# CONTROL.net
KiCad netlist of a schematic drawn in EAGLE
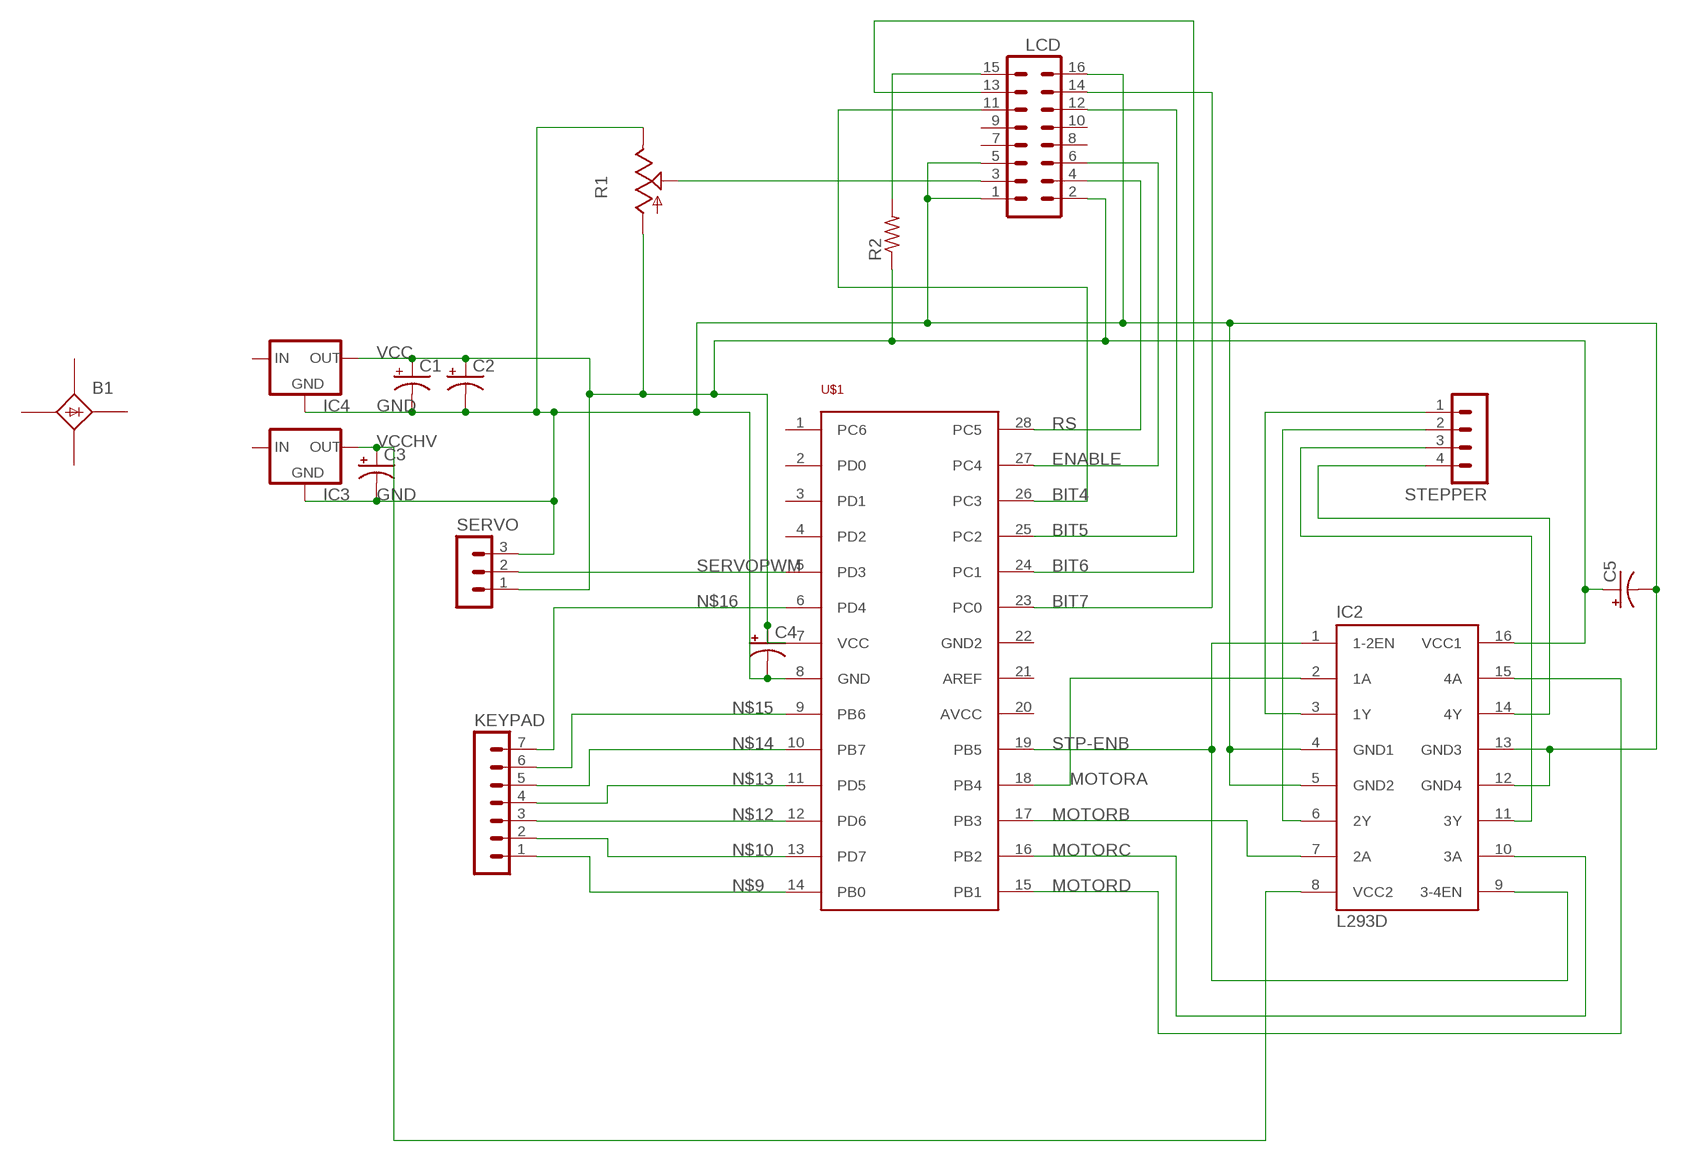
[diagram p0: schematic, sheet 1]

(export (version "E")
  (design (tool "Eeschema 10.0.6"))
  (components
    (comp (ref "B1")
      (value "B25A-")
      (footprint "eagle-import:B25A-")
      (libsource (lib "eagle-import") (part "B25A-"))
    )
    (comp (ref "C1")
      (value "CPOL-USE5-8.5")
      (footprint "eagle-import:E5-8,5")
      (libsource (lib "eagle-import") (part "CPOL-USE5-8.5"))
    )
    (comp (ref "C2")
      (value "CPOL-USE5-8.5")
      (footprint "eagle-import:E5-8,5")
      (libsource (lib "eagle-import") (part "CPOL-USE5-8.5"))
    )
    (comp (ref "C3")
      (value "CPOL-USE5-8.5")
      (footprint "eagle-import:E5-8,5")
      (libsource (lib "eagle-import") (part "CPOL-USE5-8.5"))
    )
    (comp (ref "C4")
      (value "CPOL-USE5-8.5")
      (footprint "eagle-import:E5-8,5")
      (libsource (lib "eagle-import") (part "CPOL-USE5-8.5"))
    )
    (comp (ref "C5")
      (value "CPOL-USE5-8.5")
      (footprint "eagle-import:E5-8,5")
      (libsource (lib "eagle-import") (part "CPOL-USE5-8.5"))
    )
    (comp (ref "IC2")
      (value "L293D")
      (footprint "eagle-import:DIL16")
      (libsource (lib "eagle-import") (part "L293D"))
    )
    (comp (ref "IC3")
      (value "78XXS")
      (footprint "eagle-import:78XXS")
      (libsource (lib "eagle-import") (part "78XXS"))
    )
    (comp (ref "IC4")
      (value "78XXS")
      (footprint "eagle-import:78XXS")
      (libsource (lib "eagle-import") (part "78XXS"))
    )
    (comp (ref "KEYPAD")
      (value "MA07-1")
      (footprint "eagle-import:MA07-1")
      (libsource (lib "eagle-import") (part "MA07-1"))
    )
    (comp (ref "LCD")
      (value "MA08-2")
      (footprint "eagle-import:MA08-2")
      (libsource (lib "eagle-import") (part "MA08-2"))
    )
    (comp (ref "R1")
      (value "TRIM_US-B25U")
      (footprint "eagle-import:B25U")
      (libsource (lib "eagle-import") (part "TRIM_US-B25U"))
    )
    (comp (ref "R2")
      (value "R-US_0207/10")
      (footprint "eagle-import:0207_10")
      (libsource (lib "eagle-import") (part "R-US_0207/10"))
    )
    (comp (ref "SERVO")
      (value "MA03-1")
      (footprint "eagle-import:MA03-1")
      (libsource (lib "eagle-import") (part "MA03-1"))
    )
    (comp (ref "STEPPER")
      (value "MA04-1")
      (footprint "eagle-import:MA04-1")
      (libsource (lib "eagle-import") (part "MA04-1"))
    )
    (comp (ref "U$1")
      (value "TDS")
      (footprint "eagle-import:28DIP")
      (libsource (lib "eagle-import") (part "TDS"))
    )
  )
  (nets
    (net (code "1") (name "/BIT4") (class "Default")
      (node (ref "LCD") (pin "11") (pinfunction "11_11") (pintype "passive"))
      (node (ref "U$1") (pin "26") (pinfunction "PC3_26") (pintype "bidirectional"))
    )
    (net (code "2") (name "/BIT5") (class "Default")
      (node (ref "LCD") (pin "12") (pinfunction "12_12") (pintype "passive"))
      (node (ref "U$1") (pin "25") (pinfunction "PC2_25") (pintype "bidirectional"))
    )
    (net (code "3") (name "/BIT6") (class "Default")
      (node (ref "LCD") (pin "13") (pinfunction "13_13") (pintype "passive"))
      (node (ref "U$1") (pin "24") (pinfunction "PC1_24") (pintype "bidirectional"))
    )
    (net (code "4") (name "/BIT7") (class "Default")
      (node (ref "LCD") (pin "14") (pinfunction "14_14") (pintype "passive"))
      (node (ref "U$1") (pin "23") (pinfunction "PC0_23") (pintype "bidirectional"))
    )
    (net (code "5") (name "/ENABLE") (class "Default")
      (node (ref "LCD") (pin "6") (pinfunction "6_6") (pintype "passive"))
      (node (ref "U$1") (pin "27") (pinfunction "PC4_27") (pintype "bidirectional"))
    )
    (net (code "6") (name "/GND") (class "Default")
      (node (ref "C1") (pin "-") (pinfunction "-_-") (pintype "passive"))
      (node (ref "C2") (pin "-") (pinfunction "-_-") (pintype "passive"))
      (node (ref "C3") (pin "-") (pinfunction "-_-") (pintype "passive"))
      (node (ref "C4") (pin "-") (pinfunction "-_-") (pintype "passive"))
      (node (ref "C5") (pin "-") (pinfunction "-_-") (pintype "passive"))
      (node (ref "IC2") (pin "12") (pinfunction "GND4_12") (pintype "power_in"))
      (node (ref "IC2") (pin "13") (pinfunction "GND3_13") (pintype "power_in"))
      (node (ref "IC2") (pin "4") (pinfunction "GND1_4") (pintype "power_in"))
      (node (ref "IC2") (pin "5") (pinfunction "GND2_5") (pintype "power_in"))
      (node (ref "IC3") (pin "GND") (pinfunction "GND_GND") (pintype "input"))
      (node (ref "IC4") (pin "GND") (pinfunction "GND_GND") (pintype "input"))
      (node (ref "LCD") (pin "1") (pinfunction "1_1") (pintype "passive"))
      (node (ref "LCD") (pin "16") (pinfunction "16_16") (pintype "passive"))
      (node (ref "LCD") (pin "5") (pinfunction "5_5") (pintype "passive"))
      (node (ref "R1") (pin "E") (pinfunction "E_E") (pintype "passive"))
      (node (ref "SERVO") (pin "3") (pinfunction "3_3") (pintype "passive"))
      (node (ref "U$1") (pin "8") (pinfunction "GND_8") (pintype "bidirectional"))
    )
    (net (code "7") (name "/MOTORA") (class "Default")
      (node (ref "IC2") (pin "2") (pinfunction "1A_2") (pintype "input"))
      (node (ref "U$1") (pin "18") (pinfunction "PB4_18") (pintype "bidirectional"))
    )
    (net (code "8") (name "/MOTORB") (class "Default")
      (node (ref "IC2") (pin "7") (pinfunction "2A_7") (pintype "input"))
      (node (ref "U$1") (pin "17") (pinfunction "PB3_17") (pintype "bidirectional"))
    )
    (net (code "9") (name "/MOTORC") (class "Default")
      (node (ref "IC2") (pin "10") (pinfunction "3A_10") (pintype "input"))
      (node (ref "U$1") (pin "16") (pinfunction "PB2_16") (pintype "bidirectional"))
    )
    (net (code "10") (name "/MOTORD") (class "Default")
      (node (ref "IC2") (pin "15") (pinfunction "4A_15") (pintype "input"))
      (node (ref "U$1") (pin "15") (pinfunction "PB1_15") (pintype "bidirectional"))
    )
    (net (code "11") (name "/N$9") (class "Default")
      (node (ref "KEYPAD") (pin "1") (pinfunction "1_1") (pintype "passive"))
      (node (ref "U$1") (pin "14") (pinfunction "PB0_14") (pintype "bidirectional"))
    )
    (net (code "12") (name "/N$10") (class "Default")
      (node (ref "KEYPAD") (pin "2") (pinfunction "2_2") (pintype "passive"))
      (node (ref "U$1") (pin "13") (pinfunction "PD7_13") (pintype "bidirectional"))
    )
    (net (code "13") (name "/N$12") (class "Default")
      (node (ref "KEYPAD") (pin "3") (pinfunction "3_3") (pintype "passive"))
      (node (ref "U$1") (pin "12") (pinfunction "PD6_12") (pintype "bidirectional"))
    )
    (net (code "14") (name "/N$13") (class "Default")
      (node (ref "KEYPAD") (pin "4") (pinfunction "4_4") (pintype "passive"))
      (node (ref "U$1") (pin "11") (pinfunction "PD5_11") (pintype "bidirectional"))
    )
    (net (code "15") (name "/N$14") (class "Default")
      (node (ref "KEYPAD") (pin "5") (pinfunction "5_5") (pintype "passive"))
      (node (ref "U$1") (pin "10") (pinfunction "PB7_10") (pintype "bidirectional"))
    )
    (net (code "16") (name "/N$15") (class "Default")
      (node (ref "KEYPAD") (pin "6") (pinfunction "6_6") (pintype "passive"))
      (node (ref "U$1") (pin "9") (pinfunction "PB6_9") (pintype "bidirectional"))
    )
    (net (code "17") (name "/N$16") (class "Default")
      (node (ref "KEYPAD") (pin "7") (pinfunction "7_7") (pintype "passive"))
      (node (ref "U$1") (pin "6") (pinfunction "PD4_6") (pintype "bidirectional"))
    )
    (net (code "18") (name "/RS") (class "Default")
      (node (ref "LCD") (pin "4") (pinfunction "4_4") (pintype "passive"))
      (node (ref "U$1") (pin "28") (pinfunction "PC5_28") (pintype "bidirectional"))
    )
    (net (code "19") (name "/SERVOPWM") (class "Default")
      (node (ref "SERVO") (pin "2") (pinfunction "2_2") (pintype "passive"))
      (node (ref "U$1") (pin "5") (pinfunction "PD3_5") (pintype "bidirectional"))
    )
    (net (code "20") (name "/STP-ENB") (class "Default")
      (node (ref "IC2") (pin "1") (pinfunction "1-2EN_1") (pintype "input"))
      (node (ref "IC2") (pin "9") (pinfunction "3-4EN_9") (pintype "input"))
      (node (ref "U$1") (pin "19") (pinfunction "PB5_19") (pintype "bidirectional"))
    )
    (net (code "21") (name "/VCC") (class "Default")
      (node (ref "C1") (pin "+") (pinfunction "+_+") (pintype "passive"))
      (node (ref "C2") (pin "+") (pinfunction "+_+") (pintype "passive"))
      (node (ref "C4") (pin "+") (pinfunction "+_+") (pintype "passive"))
      (node (ref "C5") (pin "+") (pinfunction "+_+") (pintype "passive"))
      (node (ref "IC2") (pin "16") (pinfunction "VCC1_16") (pintype "power_in"))
      (node (ref "IC4") (pin "OUT") (pinfunction "OUT_OUT") (pintype "passive"))
      (node (ref "LCD") (pin "2") (pinfunction "2_2") (pintype "passive"))
      (node (ref "R1") (pin "A") (pinfunction "A_A") (pintype "passive"))
      (node (ref "R2") (pin "1") (pinfunction "1_1") (pintype "passive"))
      (node (ref "SERVO") (pin "1") (pinfunction "1_1") (pintype "passive"))
      (node (ref "U$1") (pin "7") (pinfunction "VCC_7") (pintype "bidirectional"))
    )
    (net (code "22") (name "/VCCHV") (class "Default")
      (node (ref "C3") (pin "+") (pinfunction "+_+") (pintype "passive"))
      (node (ref "IC2") (pin "8") (pinfunction "VCC2_8") (pintype "power_in"))
      (node (ref "IC3") (pin "OUT") (pinfunction "OUT_OUT") (pintype "passive"))
    )
    (net (code "23") (name "Net-(IC2-1Y)") (class "Default")
      (node (ref "IC2") (pin "3") (pinfunction "1Y_3") (pintype "output"))
      (node (ref "STEPPER") (pin "1") (pinfunction "1_1") (pintype "passive"))
    )
    (net (code "24") (name "Net-(IC2-2Y)") (class "Default")
      (node (ref "IC2") (pin "6") (pinfunction "2Y_6") (pintype "output"))
      (node (ref "STEPPER") (pin "2") (pinfunction "2_2") (pintype "passive"))
    )
    (net (code "25") (name "Net-(IC2-3Y)") (class "Default")
      (node (ref "IC2") (pin "11") (pinfunction "3Y_11") (pintype "output"))
      (node (ref "STEPPER") (pin "3") (pinfunction "3_3") (pintype "passive"))
    )
    (net (code "26") (name "Net-(IC2-4Y)") (class "Default")
      (node (ref "IC2") (pin "14") (pinfunction "4Y_14") (pintype "output"))
      (node (ref "STEPPER") (pin "4") (pinfunction "4_4") (pintype "passive"))
    )
    (net (code "27") (name "Net-(LCD-Pad3)") (class "Default")
      (node (ref "LCD") (pin "3") (pinfunction "3_3") (pintype "passive"))
      (node (ref "R1") (pin "S") (pinfunction "S_S") (pintype "passive"))
    )
    (net (code "28") (name "Net-(LCD-Pad15)") (class "Default")
      (node (ref "LCD") (pin "15") (pinfunction "15_15") (pintype "passive"))
      (node (ref "R2") (pin "2") (pinfunction "2_2") (pintype "passive"))
    )
    (net (code "29") (name "unconnected-(B1-+-Pad+1)") (class "Default")
      (node (ref "B1") (pin "+1") (pinfunction "+_+1") (pintype "passive"))
    )
    (net (code "30") (name "unconnected-(B1---Pad-1)") (class "Default")
      (node (ref "B1") (pin "-1") (pinfunction "-_-1") (pintype "passive"))
    )
    (net (code "31") (name "unconnected-(B1-AC1-PadAC1-)") (class "Default")
      (node (ref "B1") (pin "AC1-") (pinfunction "AC1_AC1-") (pintype "passive"))
    )
    (net (code "32") (name "unconnected-(B1-AC2-PadAC2-)") (class "Default")
      (node (ref "B1") (pin "AC2-") (pinfunction "AC2_AC2-") (pintype "passive"))
    )
    (net (code "33") (name "unconnected-(B1-Pad+)") (class "Default")
      (node (ref "B1") (pin "+") (pinfunction "+_+") (pintype "passive"))
    )
    (net (code "34") (name "unconnected-(B1-Pad-)") (class "Default")
      (node (ref "B1") (pin "-") (pinfunction "-_-") (pintype "passive"))
    )
    (net (code "35") (name "unconnected-(B1-PadAC1)") (class "Default")
      (node (ref "B1") (pin "AC1") (pinfunction "AC1_AC1") (pintype "passive"))
    )
    (net (code "36") (name "unconnected-(B1-PadAC2)") (class "Default")
      (node (ref "B1") (pin "AC2") (pinfunction "AC2_AC2") (pintype "passive"))
    )
    (net (code "37") (name "unconnected-(IC3-PadIN)") (class "Default")
      (node (ref "IC3") (pin "IN") (pinfunction "IN_IN") (pintype "input"))
    )
    (net (code "38") (name "unconnected-(IC4-PadIN)") (class "Default")
      (node (ref "IC4") (pin "IN") (pinfunction "IN_IN") (pintype "input"))
    )
    (net (code "39") (name "unconnected-(LCD-Pad7)") (class "Default")
      (node (ref "LCD") (pin "7") (pinfunction "7_7") (pintype "passive"))
    )
    (net (code "40") (name "unconnected-(LCD-Pad8)") (class "Default")
      (node (ref "LCD") (pin "8") (pinfunction "8_8") (pintype "passive"))
    )
    (net (code "41") (name "unconnected-(LCD-Pad9)") (class "Default")
      (node (ref "LCD") (pin "9") (pinfunction "9_9") (pintype "passive"))
    )
    (net (code "42") (name "unconnected-(LCD-Pad10)") (class "Default")
      (node (ref "LCD") (pin "10") (pinfunction "10_10") (pintype "passive"))
    )
    (net (code "43") (name "unconnected-(U$1-AREF-Pad21)") (class "Default")
      (node (ref "U$1") (pin "21") (pinfunction "AREF_21") (pintype "bidirectional"))
    )
    (net (code "44") (name "unconnected-(U$1-AVCC-Pad20)") (class "Default")
      (node (ref "U$1") (pin "20") (pinfunction "AVCC_20") (pintype "bidirectional"))
    )
    (net (code "45") (name "unconnected-(U$1-GND2-Pad22)") (class "Default")
      (node (ref "U$1") (pin "22") (pinfunction "GND2_22") (pintype "bidirectional"))
    )
    (net (code "46") (name "unconnected-(U$1-PC6-Pad1)") (class "Default")
      (node (ref "U$1") (pin "1") (pinfunction "PC6_1") (pintype "bidirectional"))
    )
    (net (code "47") (name "unconnected-(U$1-PD0-Pad2)") (class "Default")
      (node (ref "U$1") (pin "2") (pinfunction "PD0_2") (pintype "bidirectional"))
    )
    (net (code "48") (name "unconnected-(U$1-PD1-Pad3)") (class "Default")
      (node (ref "U$1") (pin "3") (pinfunction "PD1_3") (pintype "bidirectional"))
    )
    (net (code "49") (name "unconnected-(U$1-PD2-Pad4)") (class "Default")
      (node (ref "U$1") (pin "4") (pinfunction "PD2_4") (pintype "bidirectional"))
    )
  )
)
